# X15-ESC-CONTROLLER.net
KiCad netlist of a schematic drawn in EAGLE
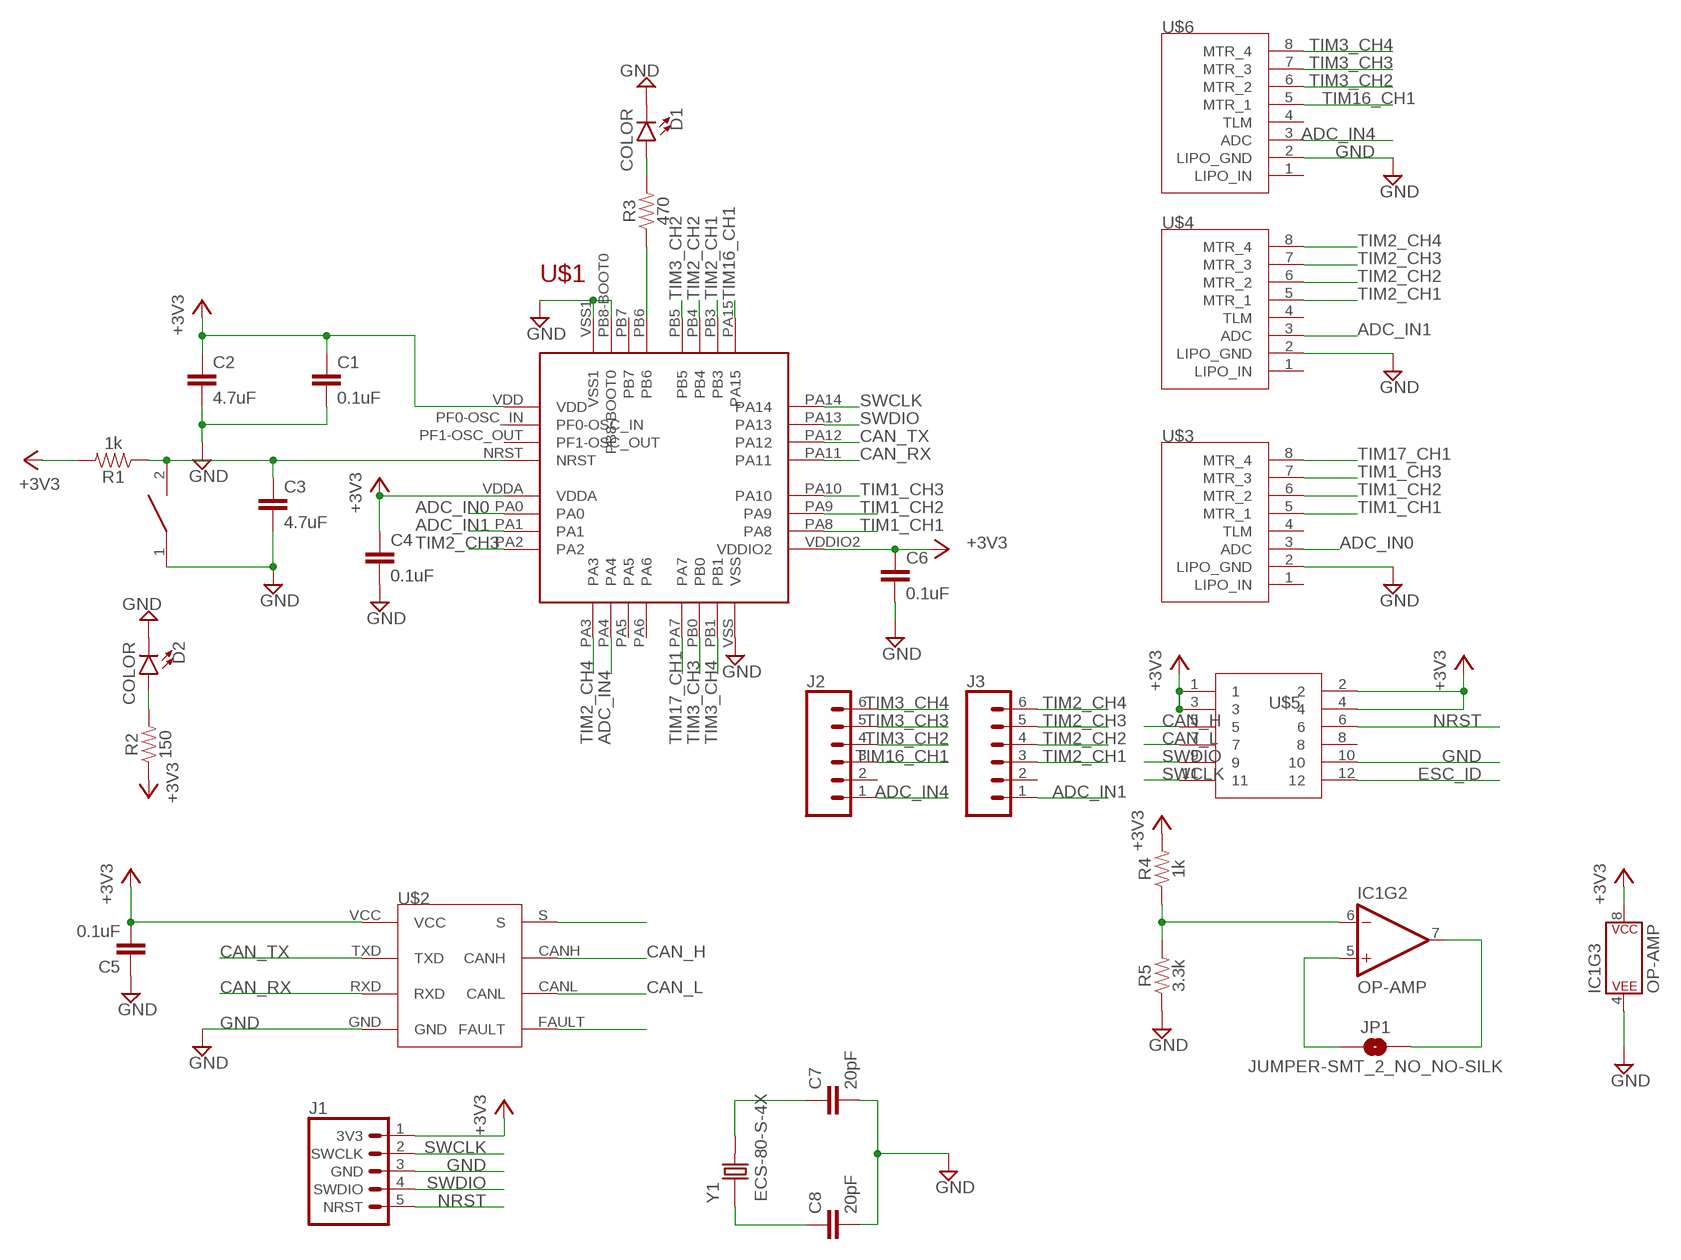
[diagram p0: schematic, sheet 1]

(export (version "E")
  (design (tool "Eeschema 10.0.6"))
  (components
    (comp (ref "C1")
      (value "0.1uF")
      (footprint "eagle-import:0603")
      (libsource (lib "eagle-import") (part "0.1UF-0603-25V-5%"))
    )
    (comp (ref "C2")
      (value "4.7uF")
      (footprint "eagle-import:0603")
      (libsource (lib "eagle-import") (part "4.7UF-0603-6.3V-(10%)"))
    )
    (comp (ref "C3")
      (value "4.7uF")
      (footprint "eagle-import:0603")
      (libsource (lib "eagle-import") (part "4.7UF-0603-6.3V-(10%)"))
    )
    (comp (ref "C4")
      (value "0.1uF")
      (footprint "eagle-import:0603")
      (libsource (lib "eagle-import") (part "0.1UF-0603-50V-10%-X7R-WE"))
    )
    (comp (ref "C5")
      (value "0.1uF")
      (footprint "eagle-import:0603")
      (libsource (lib "eagle-import") (part "0.1UF-0603-25V-(+80/-20%)"))
    )
    (comp (ref "C6")
      (value "0.1uF")
      (footprint "eagle-import:0603")
      (libsource (lib "eagle-import") (part "0.1UF-0603-25V-(+80/-20%)"))
    )
    (comp (ref "C7")
      (value "20pF")
      (footprint "eagle-import:0402-TIGHT")
      (libsource (lib "eagle-import") (part "20PF-0402T-50V-5%"))
    )
    (comp (ref "C8")
      (value "20pF")
      (footprint "eagle-import:0402-TIGHT")
      (libsource (lib "eagle-import") (part "20PF-0402T-50V-5%"))
    )
    (comp (ref "D1")
      (value "COLOR")
      (footprint "eagle-import:0805")
      (libsource (lib "eagle-import") (part "LED-0805"))
    )
    (comp (ref "D2")
      (value "COLOR")
      (footprint "eagle-import:0805")
      (libsource (lib "eagle-import") (part "LED-0805"))
    )
    (comp (ref "IC1")
      (value "OP-AMP")
      (footprint "eagle-import:SO08")
      (libsource (lib "eagle-import") (part "OPAMP-DUALU"))
    )
    (comp (ref "J1")
      (value "3V3 -SWCLK-GND-SWDIO- NRST")
      (footprint "eagle-import:1X05")
      (libsource (lib "eagle-import") (part "SWD_CONN"))
    )
    (comp (ref "J2")
      (value "CONN_06NO_SILK_NO_POP")
      (footprint "eagle-import:1X06_NO_SILK")
      (libsource (lib "eagle-import") (part "CONN_06NO_SILK_NO_POP"))
    )
    (comp (ref "J3")
      (value "CONN_06NO_SILK_NO_POP")
      (footprint "eagle-import:1X06_NO_SILK")
      (libsource (lib "eagle-import") (part "CONN_06NO_SILK_NO_POP"))
    )
    (comp (ref "JP1")
      (value "JUMPER-SMT_2_NO_NO-SILK")
      (footprint "eagle-import:SMT-JUMPER_2_NO_NO-SILK")
      (libsource (lib "eagle-import") (part "JUMPER-SMT_2_NO_NO-SILK"))
    )
    (comp (ref "R1")
      (value "1k")
      (footprint "eagle-import:0603")
      (libsource (lib "eagle-import") (part "1KOHM-0603-1/10W-1%"))
    )
    (comp (ref "R2")
      (value "150")
      (footprint "eagle-import:0603")
      (libsource (lib "eagle-import") (part "1KOHM-0603-1/10W-1%"))
    )
    (comp (ref "R3")
      (value "470")
      (footprint "eagle-import:0603")
      (libsource (lib "eagle-import") (part "10KOHM-0603-1/10W-1%"))
    )
    (comp (ref "R4")
      (value "1k")
      (footprint "eagle-import:0603")
      (libsource (lib "eagle-import") (part "1KOHM-0603-1/10W-1%"))
    )
    (comp (ref "R5")
      (value "3.3k")
      (footprint "eagle-import:0603")
      (libsource (lib "eagle-import") (part "1KOHM-0603-1/10W-1%"))
    )
    (comp (ref "U$1")
      (value "STM32F042K6T6")
      (footprint "eagle-import:STM32F042K6T6")
      (libsource (lib "eagle-import") (part "STM32F042K6T6"))
    )
    (comp (ref "U$2")
      (value "TCAN337D")
      (footprint "eagle-import:TCAN337D")
      (libsource (lib "eagle-import") (part "TCAN337D"))
    )
    (comp (ref "U$3")
      (value "JST_8_PIN")
      (footprint "eagle-import:8PIN_CONNECTOR")
      (libsource (lib "eagle-import") (part "JST_8_PIN"))
    )
    (comp (ref "U$4")
      (value "JST_8_PIN")
      (footprint "eagle-import:8PIN_CONNECTOR")
      (libsource (lib "eagle-import") (part "JST_8_PIN"))
    )
    (comp (ref "U$5")
      (value "BAKCPLANE_CONNECTOR")
      (footprint "eagle-import:BACKPLANE_CONNECTORS_BKP")
      (libsource (lib "eagle-import") (part "BAKCPLANE_CONNECTOR"))
    )
    (comp (ref "U$6")
      (value "JST_8_PIN")
      (footprint "eagle-import:8PIN_CONNECTOR")
      (libsource (lib "eagle-import") (part "JST_8_PIN"))
    )
    (comp (ref "U$7")
      (value "DISCRETECOMPONENTS_SWITCH")
      (footprint "eagle-import:DISCRETECOMPONENTS_SW_2512")
      (libsource (lib "eagle-import") (part "DISCRETECOMPONENTS_SWITCH"))
    )
    (comp (ref "Y1")
      (value "ECS-80-S-4X")
      (footprint "eagle-import:XTAL_ECS-80-S-4X")
      (fields (field (name "DIGI-KEY_PART_NUMBER") "X1057-ND") (field (name "MF") "ECS International"))
      (libsource (lib "eagle-import") (part "ECS-80-S-4X"))
    )
  )
  (nets
    (net (code "1") (name "+3V3") (class "Default")
      (node (ref "C1") (pin "1") (pinfunction "1_1") (pintype "passive"))
      (node (ref "C2") (pin "1") (pinfunction "1_1") (pintype "passive"))
      (node (ref "C4") (pin "1") (pinfunction "1_1") (pintype "passive"))
      (node (ref "C5") (pin "2") (pinfunction "2_2") (pintype "passive"))
      (node (ref "C6") (pin "1") (pinfunction "1_1") (pintype "passive"))
      (node (ref "IC1") (pin "8") (pinfunction "P$V+_8") (pintype "bidirectional"))
      (node (ref "J1") (pin "1") (pinfunction "3V3_1") (pintype "power_in"))
      (node (ref "R1") (pin "2") (pinfunction "2_2") (pintype "passive"))
      (node (ref "R2") (pin "1") (pinfunction "1_1") (pintype "passive"))
      (node (ref "R4") (pin "2") (pinfunction "2_2") (pintype "passive"))
      (node (ref "U$1") (pin "VDD") (pinfunction "VDD_VDD") (pintype "bidirectional"))
      (node (ref "U$1") (pin "VDDA") (pinfunction "VDDA_VDDA") (pintype "bidirectional"))
      (node (ref "U$1") (pin "VDDIO2") (pinfunction "VDDIO2_VDDIO2") (pintype "bidirectional"))
      (node (ref "U$2") (pin "VCC") (pinfunction "VCC_VCC") (pintype "bidirectional"))
      (node (ref "U$5") (pin "1") (pinfunction "1_1") (pintype "bidirectional"))
      (node (ref "U$5") (pin "2") (pinfunction "2_2") (pintype "bidirectional"))
      (node (ref "U$5") (pin "3") (pinfunction "3_3") (pintype "bidirectional"))
      (node (ref "U$5") (pin "4") (pinfunction "4_4") (pintype "bidirectional"))
    )
    (net (code "2") (name "/ADC_IN0") (class "Default")
      (node (ref "U$1") (pin "PA0") (pinfunction "PA0_PA0") (pintype "bidirectional"))
      (node (ref "U$3") (pin "3") (pinfunction "ADC_3") (pintype "bidirectional"))
    )
    (net (code "3") (name "/ADC_IN1") (class "Default")
      (node (ref "J3") (pin "1") (pinfunction "1_1") (pintype "passive"))
      (node (ref "U$1") (pin "PA1") (pinfunction "PA1_PA1") (pintype "bidirectional"))
      (node (ref "U$4") (pin "3") (pinfunction "ADC_3") (pintype "bidirectional"))
    )
    (net (code "4") (name "/ADC_IN4") (class "Default")
      (node (ref "J2") (pin "1") (pinfunction "1_1") (pintype "passive"))
      (node (ref "U$1") (pin "PA4") (pinfunction "PA4_PA4") (pintype "bidirectional"))
      (node (ref "U$6") (pin "3") (pinfunction "ADC_3") (pintype "bidirectional"))
    )
    (net (code "5") (name "/CAN_H") (class "Default")
      (node (ref "U$2") (pin "CANH") (pinfunction "CANH_CANH") (pintype "bidirectional"))
      (node (ref "U$5") (pin "5") (pinfunction "5_5") (pintype "bidirectional"))
    )
    (net (code "6") (name "/CAN_L") (class "Default")
      (node (ref "U$2") (pin "CANL") (pinfunction "CANL_CANL") (pintype "bidirectional"))
      (node (ref "U$5") (pin "7") (pinfunction "7_7") (pintype "bidirectional"))
    )
    (net (code "7") (name "/CAN_RX") (class "Default")
      (node (ref "U$1") (pin "PA11") (pinfunction "PA11_PA11") (pintype "bidirectional"))
      (node (ref "U$2") (pin "RXD") (pinfunction "RXD_RXD") (pintype "bidirectional"))
    )
    (net (code "8") (name "/CAN_TX") (class "Default")
      (node (ref "U$1") (pin "PA12") (pinfunction "PA12_PA12") (pintype "bidirectional"))
      (node (ref "U$2") (pin "TXD") (pinfunction "TXD_TXD") (pintype "bidirectional"))
    )
    (net (code "9") (name "/ESC_ID") (class "Default")
      (node (ref "U$5") (pin "12") (pinfunction "12_12") (pintype "bidirectional"))
    )
    (net (code "10") (name "/NRST") (class "Default")
      (node (ref "J1") (pin "5") (pinfunction "NRST_5") (pintype "open_collector"))
      (node (ref "U$5") (pin "6") (pinfunction "6_6") (pintype "bidirectional"))
    )
    (net (code "11") (name "/SWCLK") (class "Default")
      (node (ref "J1") (pin "2") (pinfunction "SWCLK_2") (pintype "input"))
      (node (ref "U$1") (pin "PA14") (pinfunction "PA14_PA14") (pintype "bidirectional"))
      (node (ref "U$5") (pin "11") (pinfunction "11_11") (pintype "bidirectional"))
    )
    (net (code "12") (name "/SWDIO") (class "Default")
      (node (ref "J1") (pin "4") (pinfunction "SWDIO_4") (pintype "bidirectional"))
      (node (ref "U$1") (pin "PA13") (pinfunction "PA13_PA13") (pintype "bidirectional"))
      (node (ref "U$5") (pin "9") (pinfunction "9_9") (pintype "bidirectional"))
    )
    (net (code "13") (name "/TIM1_CH1") (class "Default")
      (node (ref "U$1") (pin "PA8") (pinfunction "PA8_PA8") (pintype "bidirectional"))
      (node (ref "U$3") (pin "5") (pinfunction "MTR_1_5") (pintype "bidirectional"))
    )
    (net (code "14") (name "/TIM1_CH2") (class "Default")
      (node (ref "U$1") (pin "PA9") (pinfunction "PA9_PA9") (pintype "bidirectional"))
      (node (ref "U$3") (pin "6") (pinfunction "MTR_2_6") (pintype "bidirectional"))
    )
    (net (code "15") (name "/TIM1_CH3") (class "Default")
      (node (ref "U$1") (pin "PA10") (pinfunction "PA10_PA10") (pintype "bidirectional"))
      (node (ref "U$3") (pin "7") (pinfunction "MTR_3_7") (pintype "bidirectional"))
    )
    (net (code "16") (name "/TIM2_CH1") (class "Default")
      (node (ref "J3") (pin "3") (pinfunction "3_3") (pintype "passive"))
      (node (ref "U$1") (pin "PB3") (pinfunction "PB3_PB3") (pintype "bidirectional"))
      (node (ref "U$4") (pin "5") (pinfunction "MTR_1_5") (pintype "bidirectional"))
    )
    (net (code "17") (name "/TIM2_CH2") (class "Default")
      (node (ref "J3") (pin "4") (pinfunction "4_4") (pintype "passive"))
      (node (ref "U$1") (pin "PB4") (pinfunction "PB4_PB4") (pintype "bidirectional"))
      (node (ref "U$4") (pin "6") (pinfunction "MTR_2_6") (pintype "bidirectional"))
    )
    (net (code "18") (name "/TIM2_CH3") (class "Default")
      (node (ref "J3") (pin "5") (pinfunction "5_5") (pintype "passive"))
      (node (ref "U$1") (pin "PA2") (pinfunction "PA2_PA2") (pintype "bidirectional"))
      (node (ref "U$4") (pin "7") (pinfunction "MTR_3_7") (pintype "bidirectional"))
    )
    (net (code "19") (name "/TIM2_CH4") (class "Default")
      (node (ref "J3") (pin "6") (pinfunction "6_6") (pintype "passive"))
      (node (ref "U$1") (pin "PA3") (pinfunction "PA3_PA3") (pintype "bidirectional"))
      (node (ref "U$4") (pin "8") (pinfunction "MTR_4_8") (pintype "bidirectional"))
    )
    (net (code "20") (name "/TIM3_CH2") (class "Default")
      (node (ref "J2") (pin "4") (pinfunction "4_4") (pintype "passive"))
      (node (ref "U$1") (pin "PB5") (pinfunction "PB5_PB5") (pintype "bidirectional"))
      (node (ref "U$6") (pin "6") (pinfunction "MTR_2_6") (pintype "bidirectional"))
    )
    (net (code "21") (name "/TIM3_CH3") (class "Default")
      (node (ref "J2") (pin "5") (pinfunction "5_5") (pintype "passive"))
      (node (ref "U$1") (pin "PB0") (pinfunction "PB0_PB0") (pintype "bidirectional"))
      (node (ref "U$6") (pin "7") (pinfunction "MTR_3_7") (pintype "bidirectional"))
    )
    (net (code "22") (name "/TIM3_CH4") (class "Default")
      (node (ref "J2") (pin "6") (pinfunction "6_6") (pintype "passive"))
      (node (ref "U$1") (pin "PB1") (pinfunction "PB1_PB1") (pintype "bidirectional"))
      (node (ref "U$6") (pin "8") (pinfunction "MTR_4_8") (pintype "bidirectional"))
    )
    (net (code "23") (name "/TIM16_CH1") (class "Default")
      (node (ref "J2") (pin "3") (pinfunction "3_3") (pintype "passive"))
      (node (ref "U$1") (pin "PA15") (pinfunction "PA15_PA15") (pintype "bidirectional"))
      (node (ref "U$6") (pin "5") (pinfunction "MTR_1_5") (pintype "bidirectional"))
    )
    (net (code "24") (name "/TIM17_CH1") (class "Default")
      (node (ref "U$1") (pin "PA7") (pinfunction "PA7_PA7") (pintype "bidirectional"))
      (node (ref "U$3") (pin "8") (pinfunction "MTR_4_8") (pintype "bidirectional"))
    )
    (net (code "25") (name "GND") (class "Default")
      (node (ref "C1") (pin "2") (pinfunction "2_2") (pintype "passive"))
      (node (ref "C2") (pin "2") (pinfunction "2_2") (pintype "passive"))
      (node (ref "C3") (pin "2") (pinfunction "2_2") (pintype "passive"))
      (node (ref "C4") (pin "2") (pinfunction "2_2") (pintype "passive"))
      (node (ref "C5") (pin "1") (pinfunction "1_1") (pintype "passive"))
      (node (ref "C6") (pin "2") (pinfunction "2_2") (pintype "passive"))
      (node (ref "C7") (pin "2") (pinfunction "2_2") (pintype "passive"))
      (node (ref "C8") (pin "2") (pinfunction "2_2") (pintype "passive"))
      (node (ref "D1") (pin "C") (pinfunction "C_C") (pintype "passive"))
      (node (ref "D2") (pin "C") (pinfunction "C_C") (pintype "passive"))
      (node (ref "IC1") (pin "4") (pinfunction "P$V-_4") (pintype "bidirectional"))
      (node (ref "J1") (pin "3") (pinfunction "GND_3") (pintype "power_in"))
      (node (ref "R5") (pin "1") (pinfunction "1_1") (pintype "passive"))
      (node (ref "U$1") (pin "PB8-BOOT0") (pinfunction "PB8-BOOT0_PB8-BOOT0") (pintype "bidirectional"))
      (node (ref "U$1") (pin "VSS") (pinfunction "VSS_VSS") (pintype "bidirectional"))
      (node (ref "U$1") (pin "VSS1") (pinfunction "VSS1_VSS1") (pintype "bidirectional"))
      (node (ref "U$2") (pin "GND") (pinfunction "GND_GND") (pintype "bidirectional"))
      (node (ref "U$3") (pin "2") (pinfunction "LIPO_GND_2") (pintype "bidirectional"))
      (node (ref "U$4") (pin "2") (pinfunction "LIPO_GND_2") (pintype "bidirectional"))
      (node (ref "U$5") (pin "10") (pinfunction "10_10") (pintype "bidirectional"))
      (node (ref "U$6") (pin "2") (pinfunction "LIPO_GND_2") (pintype "bidirectional"))
      (node (ref "U$7") (pin "1") (pinfunction "P$1_1") (pintype "bidirectional"))
    )
    (net (code "26") (name "Net-(C7-Pad1)") (class "Default")
      (node (ref "C7") (pin "1") (pinfunction "1_1") (pintype "passive"))
      (node (ref "Y1") (pin "2") (pinfunction "2_2") (pintype "passive"))
    )
    (net (code "27") (name "Net-(C8-Pad1)") (class "Default")
      (node (ref "C8") (pin "1") (pinfunction "1_1") (pintype "passive"))
      (node (ref "Y1") (pin "1") (pinfunction "1_1") (pintype "passive"))
    )
    (net (code "28") (name "Net-(D1-PadA)") (class "Default")
      (node (ref "D1") (pin "A") (pinfunction "A_A") (pintype "passive"))
      (node (ref "R3") (pin "2") (pinfunction "2_2") (pintype "passive"))
    )
    (net (code "29") (name "Net-(D2-PadA)") (class "Default")
      (node (ref "D2") (pin "A") (pinfunction "A_A") (pintype "passive"))
      (node (ref "R2") (pin "2") (pinfunction "2_2") (pintype "passive"))
    )
    (net (code "30") (name "Net-(IC1B-+IN)") (class "Default")
      (node (ref "IC1") (pin "5") (pinfunction "+IN_5") (pintype "input"))
      (node (ref "JP1") (pin "1") (pinfunction "1_1") (pintype "passive"))
    )
    (net (code "31") (name "Net-(IC1B--IN)") (class "Default")
      (node (ref "IC1") (pin "6") (pinfunction "-IN_6") (pintype "input"))
      (node (ref "R4") (pin "1") (pinfunction "1_1") (pintype "passive"))
      (node (ref "R5") (pin "2") (pinfunction "2_2") (pintype "passive"))
    )
    (net (code "32") (name "Net-(IC1B-OUT)") (class "Default")
      (node (ref "IC1") (pin "7") (pinfunction "OUT_7") (pintype "output"))
      (node (ref "JP1") (pin "2") (pinfunction "2_2") (pintype "passive"))
    )
    (net (code "33") (name "Net-(R3-Pad1)") (class "Default")
      (node (ref "R3") (pin "1") (pinfunction "1_1") (pintype "passive"))
      (node (ref "U$1") (pin "PB6") (pinfunction "PB6_PB6") (pintype "bidirectional"))
    )
    (net (code "34") (name "Net-(U$7-P$2)") (class "Default")
      (node (ref "C3") (pin "1") (pinfunction "1_1") (pintype "passive"))
      (node (ref "R1") (pin "1") (pinfunction "1_1") (pintype "passive"))
      (node (ref "U$1") (pin "NRST") (pinfunction "NRST_NRST") (pintype "bidirectional"))
      (node (ref "U$7") (pin "2") (pinfunction "P$2_2") (pintype "bidirectional"))
    )
    (net (code "35") (name "unconnected-(J2-Pad2)") (class "Default")
      (node (ref "J2") (pin "2") (pinfunction "2_2") (pintype "passive"))
    )
    (net (code "36") (name "unconnected-(J3-Pad2)") (class "Default")
      (node (ref "J3") (pin "2") (pinfunction "2_2") (pintype "passive"))
    )
    (net (code "37") (name "unconnected-(U$1-PadPA5)") (class "Default")
      (node (ref "U$1") (pin "PA5") (pinfunction "PA5_PA5") (pintype "bidirectional"))
    )
    (net (code "38") (name "unconnected-(U$1-PadPA6)") (class "Default")
      (node (ref "U$1") (pin "PA6") (pinfunction "PA6_PA6") (pintype "bidirectional"))
    )
    (net (code "39") (name "unconnected-(U$1-PadPB7)") (class "Default")
      (node (ref "U$1") (pin "PB7") (pinfunction "PB7_PB7") (pintype "bidirectional"))
    )
    (net (code "40") (name "unconnected-(U$1-PadPF0-OSC_IN)") (class "Default")
      (node (ref "U$1") (pin "PF0-OSC_IN") (pinfunction "PF0-OSC_IN_PF0-OSC_IN") (pintype "bidirectional"))
    )
    (net (code "41") (name "unconnected-(U$1-PadPF1-OSC_OUT)") (class "Default")
      (node (ref "U$1") (pin "PF1-OSC_OUT") (pinfunction "PF1-OSC_OUT_PF1-OSC_OUT") (pintype "bidirectional"))
    )
    (net (code "42") (name "unconnected-(U$2-PadFAULT)") (class "Default")
      (node (ref "U$2") (pin "FAULT") (pinfunction "FAULT_FAULT") (pintype "bidirectional"))
    )
    (net (code "43") (name "unconnected-(U$2-PadS)") (class "Default")
      (node (ref "U$2") (pin "S") (pinfunction "S_S") (pintype "bidirectional"))
    )
    (net (code "44") (name "unconnected-(U$3-LIPO_IN-Pad1)") (class "Default")
      (node (ref "U$3") (pin "1") (pinfunction "LIPO_IN_1") (pintype "bidirectional"))
    )
    (net (code "45") (name "unconnected-(U$3-TLM-Pad4)") (class "Default")
      (node (ref "U$3") (pin "4") (pinfunction "TLM_4") (pintype "bidirectional"))
    )
    (net (code "46") (name "unconnected-(U$4-LIPO_IN-Pad1)") (class "Default")
      (node (ref "U$4") (pin "1") (pinfunction "LIPO_IN_1") (pintype "bidirectional"))
    )
    (net (code "47") (name "unconnected-(U$4-TLM-Pad4)") (class "Default")
      (node (ref "U$4") (pin "4") (pinfunction "TLM_4") (pintype "bidirectional"))
    )
    (net (code "48") (name "unconnected-(U$5-Pad8)") (class "Default")
      (node (ref "U$5") (pin "8") (pinfunction "8_8") (pintype "bidirectional"))
    )
    (net (code "49") (name "unconnected-(U$6-LIPO_IN-Pad1)") (class "Default")
      (node (ref "U$6") (pin "1") (pinfunction "LIPO_IN_1") (pintype "bidirectional"))
    )
    (net (code "50") (name "unconnected-(U$6-TLM-Pad4)") (class "Default")
      (node (ref "U$6") (pin "4") (pinfunction "TLM_4") (pintype "bidirectional"))
    )
  )
)
